# I2C_CH1.net
KiCad netlist of a schematic drawn in Altium Designer
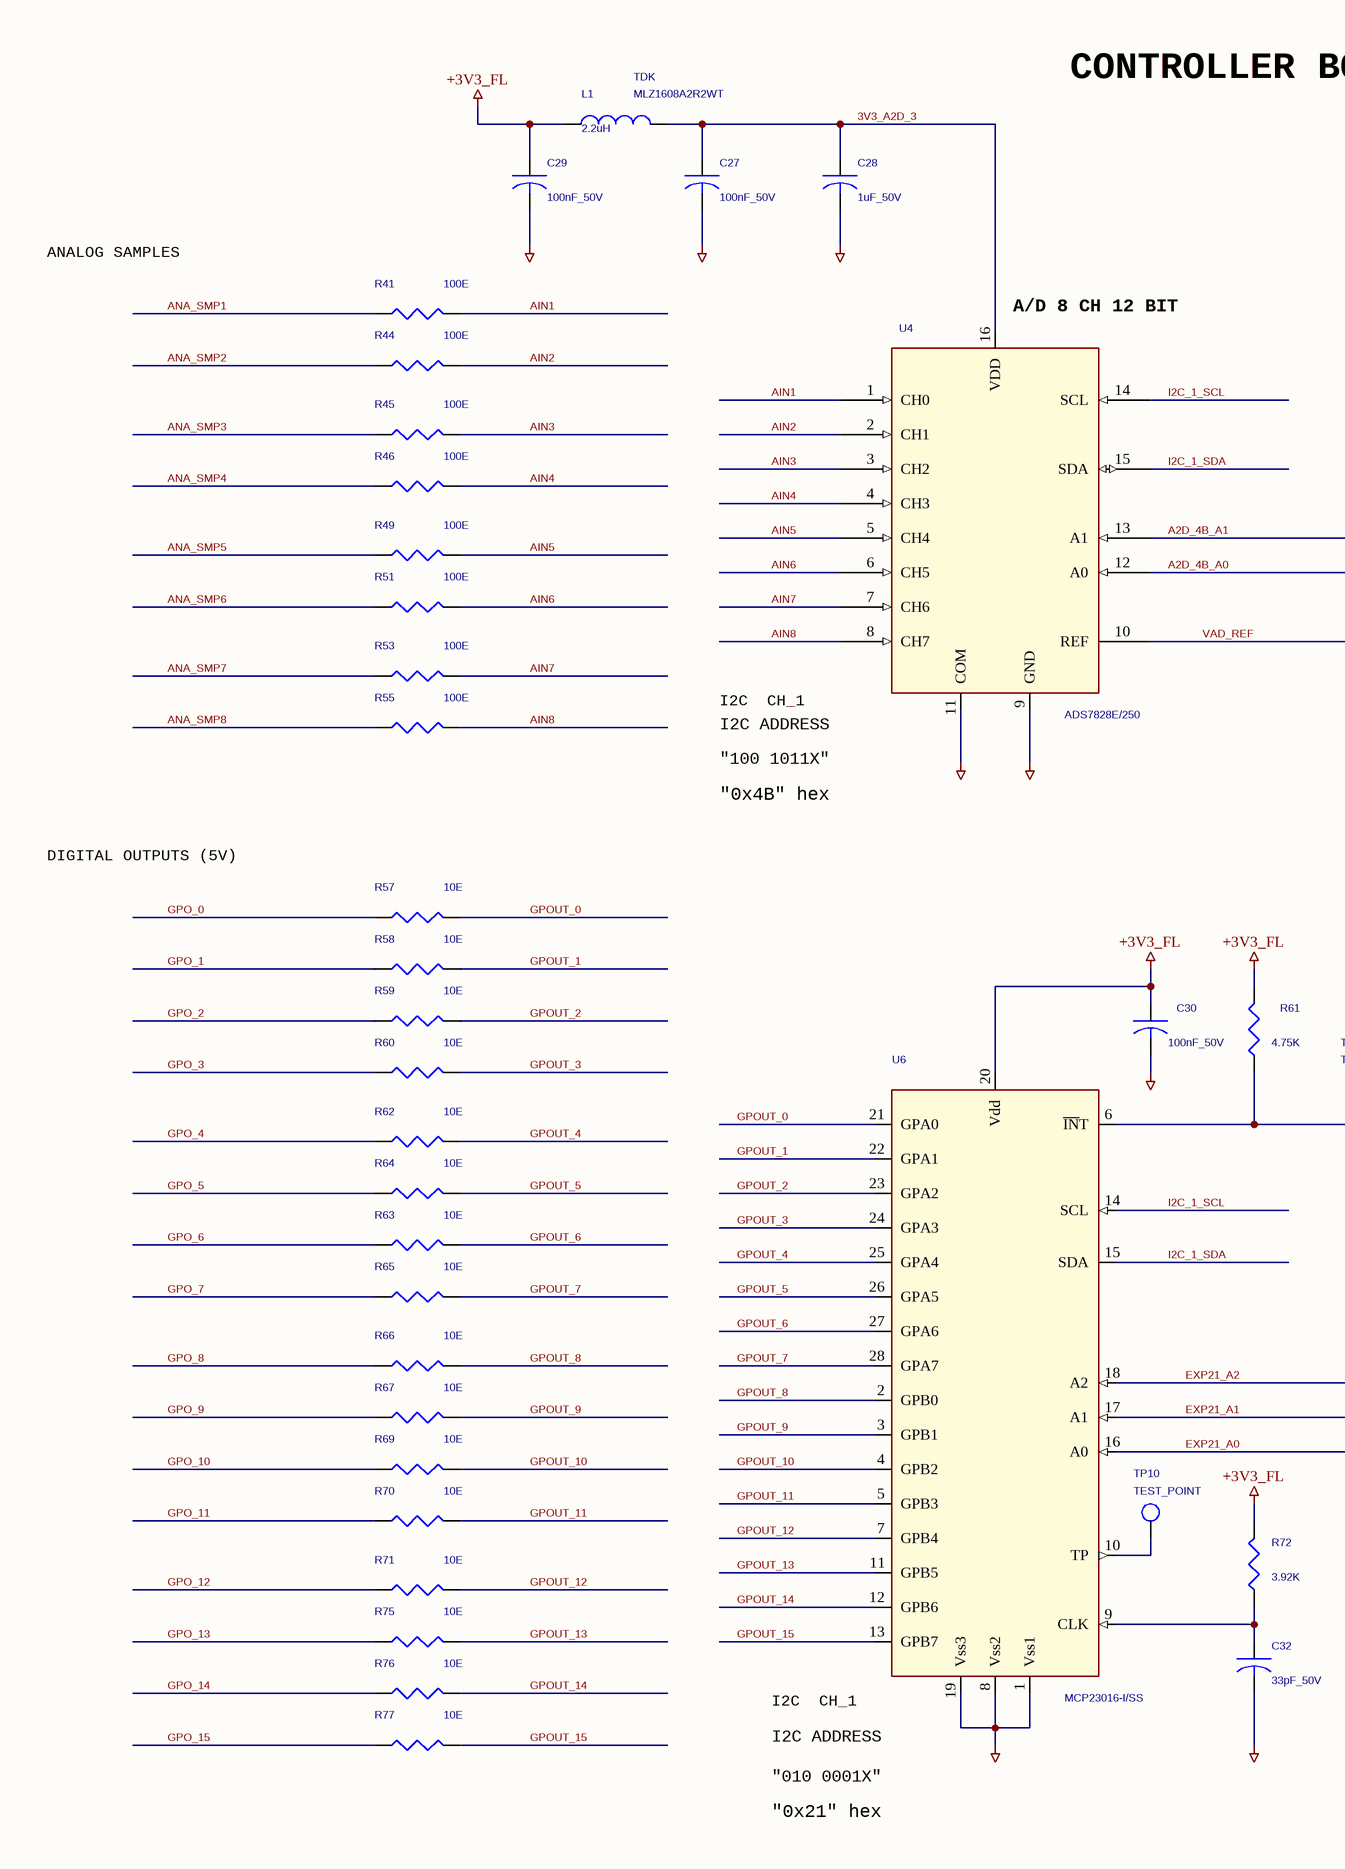
[diagram p0: I2C_CH1.SchDoc, left]
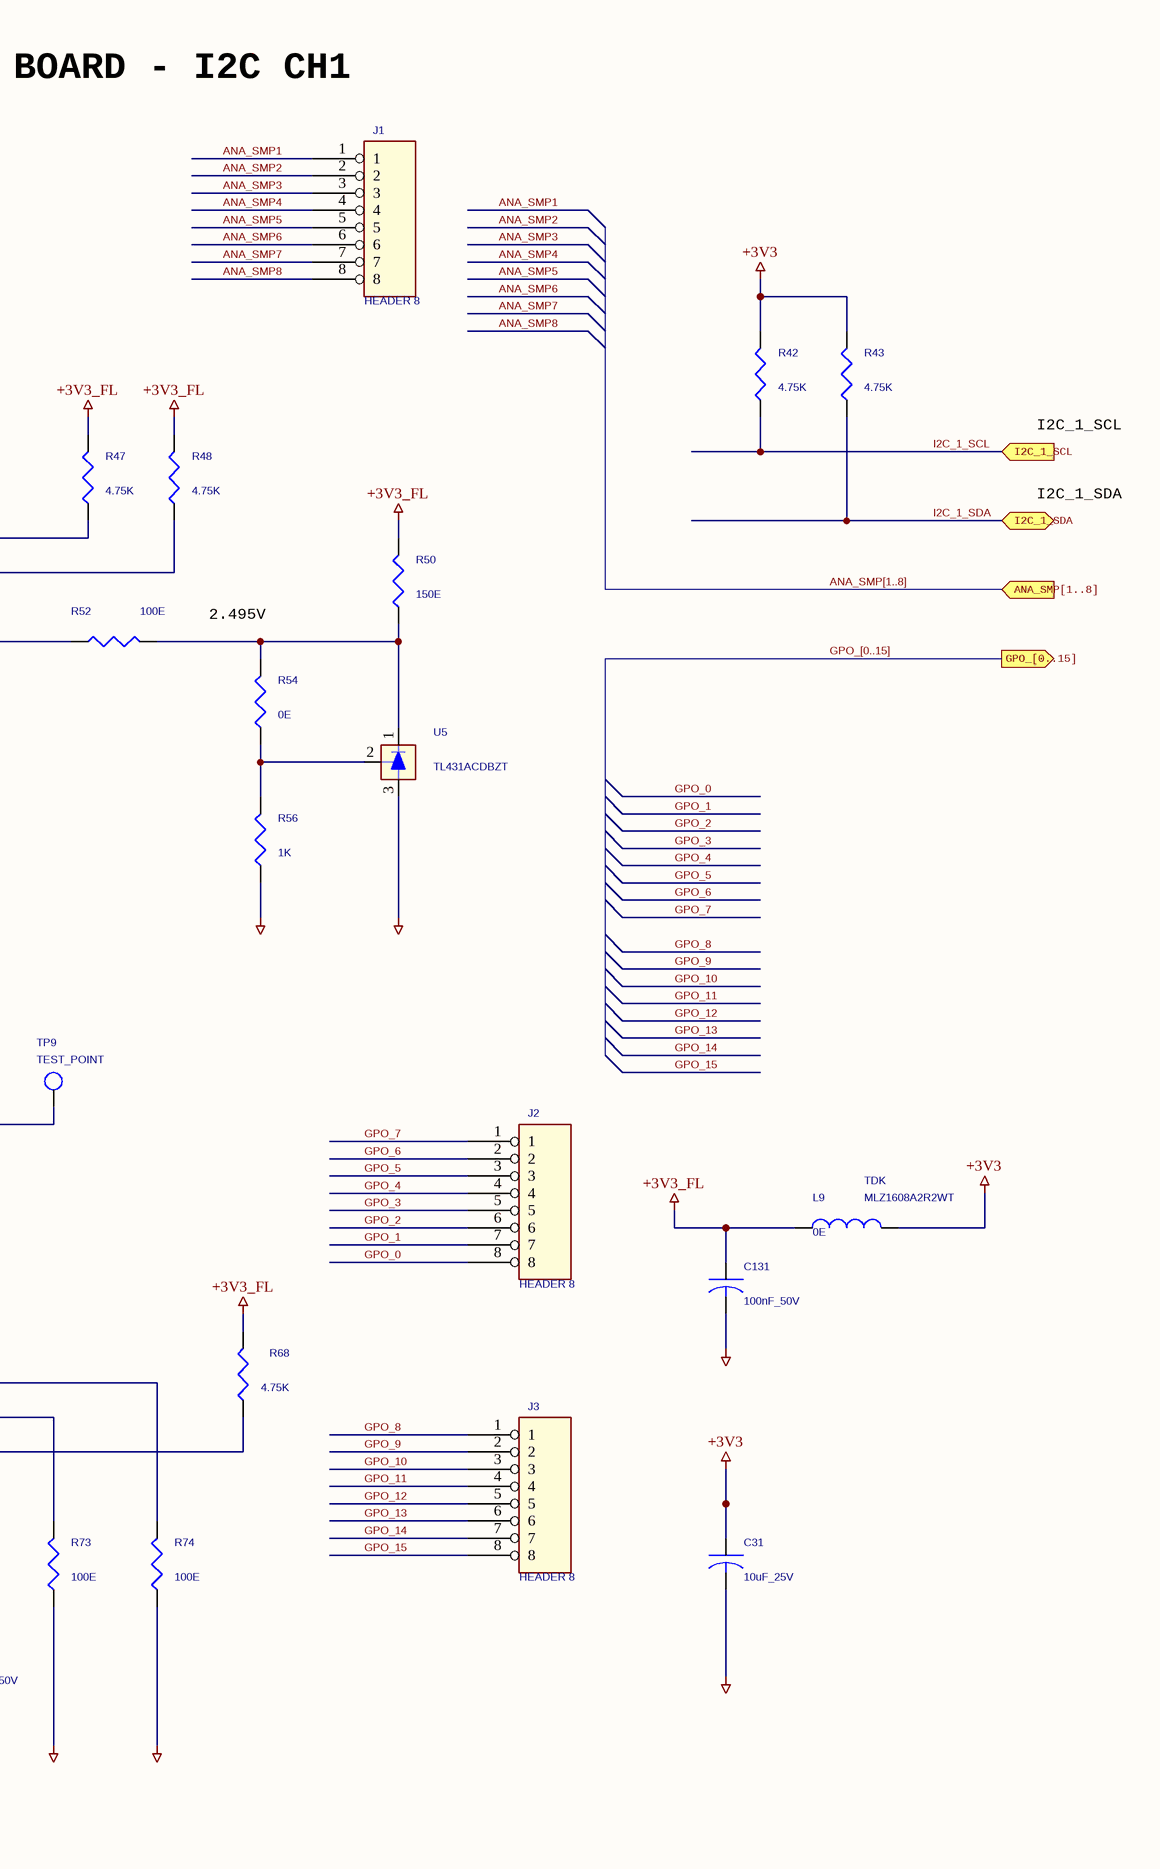
[diagram p1: I2C_CH1.SchDoc, right]

(export (version "E")
  (design (tool "Eeschema 10.0.6"))
  (components
    (comp (ref "C27")
      (value "100nF_50V")
      (footprint "0603")
      (description "CAP_SMT_0603_50V_X7R_10%")
      (fields (field (name "MFG") "KEMET"))
      (libsource (lib "*") (part "C"))
    )
    (comp (ref "C28")
      (value "1uF_50V")
      (footprint "0805")
      (description "a")
      (fields (field (name "MFG") "Murata") (field (name "MNFCTR_PART_NUMBER") "TCJT106M016R0150"))
      (libsource (lib "*") (part "CAP"))
    )
    (comp (ref "C29")
      (value "100nF_50V")
      (footprint "0603")
      (description "CAP_SMT_0603_50V_X7R_10%")
      (fields (field (name "MFG") "KEMET"))
      (libsource (lib "*") (part "C"))
    )
    (comp (ref "C30")
      (value "100nF_50V")
      (footprint "0603")
      (description "CAP_SMT_0603_50V_X7R_10%")
      (fields (field (name "MFG") "KEMET"))
      (libsource (lib "*") (part "C"))
    )
    (comp (ref "C31")
      (value "10uF_25V")
      (footprint "1206")
      (description "CAP_SMT_1206_25V_X7R_10%")
      (fields (field (name "MFG") "KEMET"))
      (libsource (lib "*") (part "C"))
    )
    (comp (ref "C32")
      (value "33pF_50V")
      (footprint "0603")
      (description "CAP_SMT_0603_50V_X7R_10%")
      (fields (field (name "MFG") "KEMET"))
      (libsource (lib "*") (part "C"))
    )
    (comp (ref "C131")
      (value "100nF_50V")
      (footprint "0603")
      (description "CAP_SMT_0603_50V_X7R_10%")
      (fields (field (name "MFG") "KEMET"))
      (libsource (lib "*") (part "C"))
    )
    (comp (ref "J1") (value "HEADER 8") (footprint "TH_8PIN_100mil") (libsource (lib "*") (part "HEADER 8")))
    (comp (ref "J2")
      (value "HEADER 8")
      (footprint "TH_8PIN_100mil")
      (libsource (lib "CONTROLLER_30") (part "HEADER 8"))
    )
    (comp (ref "J3") (value "HEADER 8") (footprint "TH_8PIN_100mil") (libsource (lib "*") (part "HEADER 8")))
    (comp (ref "L1")
      (value "2.2uH")
      (footprint "0603")
      (fields (field (name "MFG_PN") "MLZ1608A2R2WT") (field (name "MFG") "TDK"))
      (libsource (lib "*") (part "INDUCTOR"))
    )
    (comp (ref "L9")
      (value "0E")
      (footprint "0603")
      (fields (field (name "MFG") "TDK") (field (name "MFG_PN") "MLZ1608A2R2WT"))
      (libsource (lib "*") (part "INDUCTOR"))
    )
    (comp (ref "R41")
      (value "100E")
      (footprint "0603")
      (fields (field (name "MFG") "YAGEO"))
      (libsource (lib "*") (part "R_Dup1"))
    )
    (comp (ref "R42")
      (value "4.75K")
      (footprint "0603")
      (fields (field (name "MFG") "YAGEO"))
      (libsource (lib "*") (part "R_Dup1"))
    )
    (comp (ref "R43")
      (value "4.75K")
      (footprint "0603")
      (fields (field (name "MFG") "YAGEO"))
      (libsource (lib "*") (part "R_Dup1"))
    )
    (comp (ref "R44")
      (value "100E")
      (footprint "0603")
      (fields (field (name "MFG") "YAGEO"))
      (libsource (lib "*") (part "R_Dup1"))
    )
    (comp (ref "R45")
      (value "100E")
      (footprint "0603")
      (fields (field (name "MFG") "YAGEO"))
      (libsource (lib "*") (part "R_Dup1"))
    )
    (comp (ref "R46")
      (value "100E")
      (footprint "0603")
      (fields (field (name "MFG") "YAGEO"))
      (libsource (lib "*") (part "R_Dup1"))
    )
    (comp (ref "R47")
      (value "4.75K")
      (footprint "0603")
      (fields (field (name "MFG") "YAGEO"))
      (libsource (lib "*") (part "R_Dup1"))
    )
    (comp (ref "R48")
      (value "4.75K")
      (footprint "0603")
      (fields (field (name "MFG") "YAGEO"))
      (libsource (lib "*") (part "R_Dup1"))
    )
    (comp (ref "R49")
      (value "100E")
      (footprint "0603")
      (fields (field (name "MFG") "YAGEO"))
      (libsource (lib "*") (part "R_Dup1"))
    )
    (comp (ref "R50")
      (value "150E")
      (footprint "0603")
      (fields (field (name "MFG") "YAGEO"))
      (libsource (lib "*") (part "R_Dup1"))
    )
    (comp (ref "R51")
      (value "100E")
      (footprint "0603")
      (fields (field (name "MFG") "YAGEO"))
      (libsource (lib "*") (part "R_Dup1"))
    )
    (comp (ref "R52")
      (value "100E")
      (footprint "0603")
      (fields (field (name "MFG") "YAGEO"))
      (libsource (lib "*") (part "R_Dup1"))
    )
    (comp (ref "R53")
      (value "100E")
      (footprint "0603")
      (fields (field (name "MFG") "YAGEO"))
      (libsource (lib "*") (part "R_Dup1"))
    )
    (comp (ref "R54")
      (value "0E")
      (footprint "0603")
      (fields (field (name "MFG") "YAGEO"))
      (libsource (lib "*") (part "R_Dup1"))
    )
    (comp (ref "R55")
      (value "100E")
      (footprint "0603")
      (fields (field (name "MFG") "YAGEO"))
      (libsource (lib "*") (part "R_Dup1"))
    )
    (comp (ref "R56")
      (value "1K")
      (footprint "0603")
      (fields (field (name "MFG") "YAGEO"))
      (libsource (lib "*") (part "R_Dup1"))
    )
    (comp (ref "R57")
      (value "10E")
      (footprint "0603")
      (fields (field (name "MFG") "YAGEO"))
      (libsource (lib "*") (part "R_Dup1"))
    )
    (comp (ref "R58")
      (value "10E")
      (footprint "0603")
      (fields (field (name "MFG") "YAGEO"))
      (libsource (lib "*") (part "R_Dup1"))
    )
    (comp (ref "R59")
      (value "10E")
      (footprint "0603")
      (fields (field (name "MFG") "YAGEO"))
      (libsource (lib "*") (part "R_Dup1"))
    )
    (comp (ref "R60")
      (value "10E")
      (footprint "0603")
      (fields (field (name "MFG") "YAGEO"))
      (libsource (lib "*") (part "R_Dup1"))
    )
    (comp (ref "R61")
      (value "4.75K")
      (footprint "0603")
      (fields (field (name "MFG") "YAGEO"))
      (libsource (lib "*") (part "R_Dup1"))
    )
    (comp (ref "R62")
      (value "10E")
      (footprint "0603")
      (fields (field (name "MFG") "YAGEO"))
      (libsource (lib "*") (part "R_Dup1"))
    )
    (comp (ref "R63")
      (value "10E")
      (footprint "0603")
      (fields (field (name "MFG") "YAGEO"))
      (libsource (lib "*") (part "R_Dup1"))
    )
    (comp (ref "R64")
      (value "10E")
      (footprint "0603")
      (fields (field (name "MFG") "YAGEO"))
      (libsource (lib "*") (part "R_Dup1"))
    )
    (comp (ref "R65")
      (value "10E")
      (footprint "0603")
      (fields (field (name "MFG") "YAGEO"))
      (libsource (lib "*") (part "R_Dup1"))
    )
    (comp (ref "R66")
      (value "10E")
      (footprint "0603")
      (fields (field (name "MFG") "YAGEO"))
      (libsource (lib "*") (part "R_Dup1"))
    )
    (comp (ref "R67")
      (value "10E")
      (footprint "0603")
      (fields (field (name "MFG") "YAGEO"))
      (libsource (lib "*") (part "R_Dup1"))
    )
    (comp (ref "R68")
      (value "4.75K")
      (footprint "0603")
      (fields (field (name "MFG") "YAGEO"))
      (libsource (lib "*") (part "R_Dup1"))
    )
    (comp (ref "R69")
      (value "10E")
      (footprint "0603")
      (fields (field (name "MFG") "YAGEO"))
      (libsource (lib "*") (part "R_Dup1"))
    )
    (comp (ref "R70")
      (value "10E")
      (footprint "0603")
      (fields (field (name "MFG") "YAGEO"))
      (libsource (lib "*") (part "R_Dup1"))
    )
    (comp (ref "R71")
      (value "10E")
      (footprint "0603")
      (fields (field (name "MFG") "YAGEO"))
      (libsource (lib "*") (part "R_Dup1"))
    )
    (comp (ref "R72")
      (value "3.92K")
      (footprint "0603")
      (fields (field (name "MFG") "YAGEO"))
      (libsource (lib "*") (part "R_Dup1"))
    )
    (comp (ref "R73")
      (value "100E")
      (footprint "0603")
      (fields (field (name "MFG") "YAGEO"))
      (libsource (lib "*") (part "R_Dup1"))
    )
    (comp (ref "R74")
      (value "100E")
      (footprint "0603")
      (fields (field (name "MFG") "YAGEO"))
      (libsource (lib "*") (part "R_Dup1"))
    )
    (comp (ref "R75")
      (value "10E")
      (footprint "0603")
      (fields (field (name "MFG") "YAGEO"))
      (libsource (lib "*") (part "R_Dup1"))
    )
    (comp (ref "R76")
      (value "10E")
      (footprint "0603")
      (fields (field (name "MFG") "YAGEO"))
      (libsource (lib "*") (part "R_Dup1"))
    )
    (comp (ref "R77")
      (value "10E")
      (footprint "0603")
      (fields (field (name "MFG") "YAGEO"))
      (libsource (lib "*") (part "R_Dup1"))
    )
    (comp (ref "TP9") (value "TEST_POINT") (footprint "TH_1mm") (libsource (lib "*") (part "T POINT R_Dup1")))
    (comp (ref "TP10")
      (value "TEST_POINT")
      (footprint "TH_1mm")
      (libsource (lib "*") (part "T POINT R_Dup1"))
    )
    (comp (ref "U4")
      (value "ADS7828E/250")
      (footprint "TSSOP_16")
      (fields (field (name "MFG") "TI"))
      (libsource (lib "*") (part "ADS7828E"))
    )
    (comp (ref "U5")
      (value "TL431ACDBZT")
      (footprint "SOT_23")
      (fields (field (name "PART_NUMBER") "<Part_Number>") (field (name "MFG") "TI"))
      (libsource (lib "*") (part "TL431ACDBZT"))
    )
    (comp (ref "U6")
      (value "MCP23016-I/SS")
      (footprint "SSOP_28")
      (fields (field (name "MFG") "MICROCHIP"))
      (libsource (lib "*") (part "MCP23016-I/SS"))
    )
  )
  (nets
    (net (code "1") (name "+3V3") (class "Default")
      (node (ref "C31") (pin "1") (pinfunction "1_1") (pintype "passive"))
      (node (ref "L9") (pin "2") (pinfunction "2_2") (pintype "passive"))
      (node (ref "R42") (pin "2") (pinfunction "2_2") (pintype "passive"))
      (node (ref "R43") (pin "2") (pinfunction "2_2") (pintype "passive"))
    )
    (net (code "2") (name "+3V3_FL") (class "Default")
      (node (ref "C131") (pin "1") (pinfunction "1_1") (pintype "passive"))
      (node (ref "C29") (pin "1") (pinfunction "1_1") (pintype "passive"))
      (node (ref "C30") (pin "1") (pinfunction "1_1") (pintype "passive"))
      (node (ref "L1") (pin "1") (pinfunction "1_1") (pintype "passive"))
      (node (ref "L9") (pin "1") (pinfunction "1_1") (pintype "passive"))
      (node (ref "R47") (pin "2") (pinfunction "2_2") (pintype "passive"))
      (node (ref "R48") (pin "2") (pinfunction "2_2") (pintype "passive"))
      (node (ref "R50") (pin "2") (pinfunction "2_2") (pintype "passive"))
      (node (ref "R61") (pin "2") (pinfunction "2_2") (pintype "passive"))
      (node (ref "R68") (pin "2") (pinfunction "2_2") (pintype "passive"))
      (node (ref "R72") (pin "2") (pinfunction "2_2") (pintype "passive"))
      (node (ref "U6") (pin "20") (pinfunction "Vdd_20") (pintype "passive"))
    )
    (net (code "3") (name "/3V3_A2D_3") (class "Default")
      (node (ref "C27") (pin "1") (pinfunction "1_1") (pintype "passive"))
      (node (ref "C28") (pin "1") (pinfunction "1_1") (pintype "passive"))
      (node (ref "L1") (pin "2") (pinfunction "2_2") (pintype "passive"))
      (node (ref "U4") (pin "16") (pinfunction "VDD_16") (pintype "passive"))
    )
    (net (code "4") (name "/A2D_4B_A0") (class "Default")
      (node (ref "R48") (pin "1") (pinfunction "1_1") (pintype "passive"))
      (node (ref "U4") (pin "12") (pinfunction "A0_12") (pintype "input"))
    )
    (net (code "5") (name "/A2D_4B_A1") (class "Default")
      (node (ref "R47") (pin "1") (pinfunction "1_1") (pintype "passive"))
      (node (ref "U4") (pin "13") (pinfunction "A1_13") (pintype "input"))
    )
    (net (code "6") (name "/AIN1") (class "Default")
      (node (ref "R41") (pin "1") (pinfunction "1_1") (pintype "passive"))
      (node (ref "U4") (pin "1") (pinfunction "CH0_1") (pintype "input"))
    )
    (net (code "7") (name "/AIN2") (class "Default")
      (node (ref "R44") (pin "1") (pinfunction "1_1") (pintype "passive"))
      (node (ref "U4") (pin "2") (pinfunction "CH1_2") (pintype "input"))
    )
    (net (code "8") (name "/AIN3") (class "Default")
      (node (ref "R45") (pin "1") (pinfunction "1_1") (pintype "passive"))
      (node (ref "U4") (pin "3") (pinfunction "CH2_3") (pintype "input"))
    )
    (net (code "9") (name "/AIN4") (class "Default")
      (node (ref "R46") (pin "1") (pinfunction "1_1") (pintype "passive"))
      (node (ref "U4") (pin "4") (pinfunction "CH3_4") (pintype "input"))
    )
    (net (code "10") (name "/AIN5") (class "Default")
      (node (ref "R49") (pin "1") (pinfunction "1_1") (pintype "passive"))
      (node (ref "U4") (pin "5") (pinfunction "CH4_5") (pintype "input"))
    )
    (net (code "11") (name "/AIN6") (class "Default")
      (node (ref "R51") (pin "1") (pinfunction "1_1") (pintype "passive"))
      (node (ref "U4") (pin "6") (pinfunction "CH5_6") (pintype "input"))
    )
    (net (code "12") (name "/AIN7") (class "Default")
      (node (ref "R53") (pin "1") (pinfunction "1_1") (pintype "passive"))
      (node (ref "U4") (pin "7") (pinfunction "CH6_7") (pintype "input"))
    )
    (net (code "13") (name "/AIN8") (class "Default")
      (node (ref "R55") (pin "1") (pinfunction "1_1") (pintype "passive"))
      (node (ref "U4") (pin "8") (pinfunction "CH7_8") (pintype "input"))
    )
    (net (code "14") (name "/ANA_SMP1") (class "Default")
      (node (ref "J1") (pin "1") (pinfunction "1_1") (pintype "passive"))
      (node (ref "R41") (pin "2") (pinfunction "2_2") (pintype "passive"))
    )
    (net (code "15") (name "/ANA_SMP2") (class "Default")
      (node (ref "J1") (pin "2") (pinfunction "2_2") (pintype "passive"))
      (node (ref "R44") (pin "2") (pinfunction "2_2") (pintype "passive"))
    )
    (net (code "16") (name "/ANA_SMP3") (class "Default")
      (node (ref "J1") (pin "3") (pinfunction "3_3") (pintype "passive"))
      (node (ref "R45") (pin "2") (pinfunction "2_2") (pintype "passive"))
    )
    (net (code "17") (name "/ANA_SMP4") (class "Default")
      (node (ref "J1") (pin "4") (pinfunction "4_4") (pintype "passive"))
      (node (ref "R46") (pin "2") (pinfunction "2_2") (pintype "passive"))
    )
    (net (code "18") (name "/ANA_SMP5") (class "Default")
      (node (ref "J1") (pin "5") (pinfunction "5_5") (pintype "passive"))
      (node (ref "R49") (pin "2") (pinfunction "2_2") (pintype "passive"))
    )
    (net (code "19") (name "/ANA_SMP6") (class "Default")
      (node (ref "J1") (pin "6") (pinfunction "6_6") (pintype "passive"))
      (node (ref "R51") (pin "2") (pinfunction "2_2") (pintype "passive"))
    )
    (net (code "20") (name "/ANA_SMP7") (class "Default")
      (node (ref "J1") (pin "7") (pinfunction "7_7") (pintype "passive"))
      (node (ref "R53") (pin "2") (pinfunction "2_2") (pintype "passive"))
    )
    (net (code "21") (name "/ANA_SMP8") (class "Default")
      (node (ref "J1") (pin "8") (pinfunction "8_8") (pintype "passive"))
      (node (ref "R55") (pin "2") (pinfunction "2_2") (pintype "passive"))
    )
    (net (code "23") (name "/EXP21_A0") (class "Default")
      (node (ref "R68") (pin "1") (pinfunction "1_1") (pintype "passive"))
      (node (ref "U6") (pin "16") (pinfunction "A0_16") (pintype "input"))
    )
    (net (code "24") (name "/EXP21_A1") (class "Default")
      (node (ref "R73") (pin "2") (pinfunction "2_2") (pintype "passive"))
      (node (ref "U6") (pin "17") (pinfunction "A1_17") (pintype "input"))
    )
    (net (code "25") (name "/EXP21_A2") (class "Default")
      (node (ref "R74") (pin "2") (pinfunction "2_2") (pintype "passive"))
      (node (ref "U6") (pin "18") (pinfunction "A2_18") (pintype "input"))
    )
    (net (code "26") (name "/GPOUT_0") (class "Default")
      (node (ref "R57") (pin "1") (pinfunction "1_1") (pintype "passive"))
      (node (ref "U6") (pin "21") (pinfunction "GPA0_21") (pintype "bidirectional"))
    )
    (net (code "27") (name "/GPOUT_1") (class "Default")
      (node (ref "R58") (pin "1") (pinfunction "1_1") (pintype "passive"))
      (node (ref "U6") (pin "22") (pinfunction "GPA1_22") (pintype "bidirectional"))
    )
    (net (code "28") (name "/GPOUT_2") (class "Default")
      (node (ref "R59") (pin "1") (pinfunction "1_1") (pintype "passive"))
      (node (ref "U6") (pin "23") (pinfunction "GPA2_23") (pintype "bidirectional"))
    )
    (net (code "29") (name "/GPOUT_3") (class "Default")
      (node (ref "R60") (pin "1") (pinfunction "1_1") (pintype "passive"))
      (node (ref "U6") (pin "24") (pinfunction "GPA3_24") (pintype "bidirectional"))
    )
    (net (code "30") (name "/GPOUT_4") (class "Default")
      (node (ref "R62") (pin "1") (pinfunction "1_1") (pintype "passive"))
      (node (ref "U6") (pin "25") (pinfunction "GPA4_25") (pintype "bidirectional"))
    )
    (net (code "31") (name "/GPOUT_5") (class "Default")
      (node (ref "R64") (pin "1") (pinfunction "1_1") (pintype "passive"))
      (node (ref "U6") (pin "26") (pinfunction "GPA5_26") (pintype "bidirectional"))
    )
    (net (code "32") (name "/GPOUT_6") (class "Default")
      (node (ref "R63") (pin "1") (pinfunction "1_1") (pintype "passive"))
      (node (ref "U6") (pin "27") (pinfunction "GPA6_27") (pintype "bidirectional"))
    )
    (net (code "33") (name "/GPOUT_7") (class "Default")
      (node (ref "R65") (pin "1") (pinfunction "1_1") (pintype "passive"))
      (node (ref "U6") (pin "28") (pinfunction "GPA7_28") (pintype "bidirectional"))
    )
    (net (code "34") (name "/GPOUT_8") (class "Default")
      (node (ref "R66") (pin "1") (pinfunction "1_1") (pintype "passive"))
      (node (ref "U6") (pin "2") (pinfunction "GPB0_2") (pintype "bidirectional"))
    )
    (net (code "35") (name "/GPOUT_9") (class "Default")
      (node (ref "R67") (pin "1") (pinfunction "1_1") (pintype "passive"))
      (node (ref "U6") (pin "3") (pinfunction "GPB1_3") (pintype "bidirectional"))
    )
    (net (code "36") (name "/GPOUT_10") (class "Default")
      (node (ref "R69") (pin "1") (pinfunction "1_1") (pintype "passive"))
      (node (ref "U6") (pin "4") (pinfunction "GPB2_4") (pintype "bidirectional"))
    )
    (net (code "37") (name "/GPOUT_11") (class "Default")
      (node (ref "R70") (pin "1") (pinfunction "1_1") (pintype "passive"))
      (node (ref "U6") (pin "5") (pinfunction "GPB3_5") (pintype "bidirectional"))
    )
    (net (code "38") (name "/GPOUT_12") (class "Default")
      (node (ref "R71") (pin "1") (pinfunction "1_1") (pintype "passive"))
      (node (ref "U6") (pin "7") (pinfunction "GPB4_7") (pintype "bidirectional"))
    )
    (net (code "39") (name "/GPOUT_13") (class "Default")
      (node (ref "R75") (pin "1") (pinfunction "1_1") (pintype "passive"))
      (node (ref "U6") (pin "11") (pinfunction "GPB5_11") (pintype "bidirectional"))
    )
    (net (code "40") (name "/GPOUT_14") (class "Default")
      (node (ref "R76") (pin "1") (pinfunction "1_1") (pintype "passive"))
      (node (ref "U6") (pin "12") (pinfunction "GPB6_12") (pintype "bidirectional"))
    )
    (net (code "41") (name "/GPOUT_15") (class "Default")
      (node (ref "R77") (pin "1") (pinfunction "1_1") (pintype "passive"))
      (node (ref "U6") (pin "13") (pinfunction "GPB7_13") (pintype "bidirectional"))
    )
    (net (code "42") (name "/GPO_0") (class "Default")
      (node (ref "J2") (pin "8") (pinfunction "8_8") (pintype "passive"))
      (node (ref "R57") (pin "2") (pinfunction "2_2") (pintype "passive"))
    )
    (net (code "43") (name "/GPO_1") (class "Default")
      (node (ref "J2") (pin "7") (pinfunction "7_7") (pintype "passive"))
      (node (ref "R58") (pin "2") (pinfunction "2_2") (pintype "passive"))
    )
    (net (code "44") (name "/GPO_2") (class "Default")
      (node (ref "J2") (pin "6") (pinfunction "6_6") (pintype "passive"))
      (node (ref "R59") (pin "2") (pinfunction "2_2") (pintype "passive"))
    )
    (net (code "45") (name "/GPO_3") (class "Default")
      (node (ref "J2") (pin "5") (pinfunction "5_5") (pintype "passive"))
      (node (ref "R60") (pin "2") (pinfunction "2_2") (pintype "passive"))
    )
    (net (code "46") (name "/GPO_4") (class "Default")
      (node (ref "J2") (pin "4") (pinfunction "4_4") (pintype "passive"))
      (node (ref "R62") (pin "2") (pinfunction "2_2") (pintype "passive"))
    )
    (net (code "47") (name "/GPO_5") (class "Default")
      (node (ref "J2") (pin "3") (pinfunction "3_3") (pintype "passive"))
      (node (ref "R64") (pin "2") (pinfunction "2_2") (pintype "passive"))
    )
    (net (code "48") (name "/GPO_6") (class "Default")
      (node (ref "J2") (pin "2") (pinfunction "2_2") (pintype "passive"))
      (node (ref "R63") (pin "2") (pinfunction "2_2") (pintype "passive"))
    )
    (net (code "49") (name "/GPO_7") (class "Default")
      (node (ref "J2") (pin "1") (pinfunction "1_1") (pintype "passive"))
      (node (ref "R65") (pin "2") (pinfunction "2_2") (pintype "passive"))
    )
    (net (code "50") (name "/GPO_8") (class "Default")
      (node (ref "J3") (pin "1") (pinfunction "1_1") (pintype "passive"))
      (node (ref "R66") (pin "2") (pinfunction "2_2") (pintype "passive"))
    )
    (net (code "51") (name "/GPO_9") (class "Default")
      (node (ref "J3") (pin "2") (pinfunction "2_2") (pintype "passive"))
      (node (ref "R67") (pin "2") (pinfunction "2_2") (pintype "passive"))
    )
    (net (code "52") (name "/GPO_10") (class "Default")
      (node (ref "J3") (pin "3") (pinfunction "3_3") (pintype "passive"))
      (node (ref "R69") (pin "2") (pinfunction "2_2") (pintype "passive"))
    )
    (net (code "53") (name "/GPO_11") (class "Default")
      (node (ref "J3") (pin "4") (pinfunction "4_4") (pintype "passive"))
      (node (ref "R70") (pin "2") (pinfunction "2_2") (pintype "passive"))
    )
    (net (code "54") (name "/GPO_12") (class "Default")
      (node (ref "J3") (pin "5") (pinfunction "5_5") (pintype "passive"))
      (node (ref "R71") (pin "2") (pinfunction "2_2") (pintype "passive"))
    )
    (net (code "55") (name "/GPO_13") (class "Default")
      (node (ref "J3") (pin "6") (pinfunction "6_6") (pintype "passive"))
      (node (ref "R75") (pin "2") (pinfunction "2_2") (pintype "passive"))
    )
    (net (code "56") (name "/GPO_14") (class "Default")
      (node (ref "J3") (pin "7") (pinfunction "7_7") (pintype "passive"))
      (node (ref "R76") (pin "2") (pinfunction "2_2") (pintype "passive"))
    )
    (net (code "57") (name "/GPO_15") (class "Default")
      (node (ref "J3") (pin "8") (pinfunction "8_8") (pintype "passive"))
      (node (ref "R77") (pin "2") (pinfunction "2_2") (pintype "passive"))
    )
    (net (code "59") (name "/I2C_1_SCL") (class "Default")
      (node (ref "R42") (pin "1") (pinfunction "1_1") (pintype "passive"))
      (node (ref "U4") (pin "14") (pinfunction "SCL_14") (pintype "input"))
      (node (ref "U6") (pin "14") (pinfunction "SCL_14") (pintype "input"))
    )
    (net (code "60") (name "/I2C_1_SDA") (class "Default")
      (node (ref "R43") (pin "1") (pinfunction "1_1") (pintype "passive"))
      (node (ref "U4") (pin "15") (pinfunction "SDA_15") (pintype "bidirectional"))
      (node (ref "U6") (pin "15") (pinfunction "SDA_15") (pintype "bidirectional"))
    )
    (net (code "61") (name "/VAD_REF") (class "Default")
      (node (ref "R52") (pin "2") (pinfunction "2_2") (pintype "passive"))
      (node (ref "U4") (pin "10") (pinfunction "REF_10") (pintype "passive"))
    )
    (net (code "62") (name "GND_CPU") (class "Default")
      (node (ref "C131") (pin "2") (pinfunction "2_2") (pintype "passive"))
      (node (ref "C27") (pin "2") (pinfunction "2_2") (pintype "passive"))
      (node (ref "C28") (pin "2") (pinfunction "2_2") (pintype "passive"))
      (node (ref "C29") (pin "2") (pinfunction "2_2") (pintype "passive"))
      (node (ref "C30") (pin "2") (pinfunction "2_2") (pintype "passive"))
      (node (ref "C31") (pin "2") (pinfunction "2_2") (pintype "passive"))
      (node (ref "C32") (pin "2") (pinfunction "2_2") (pintype "passive"))
      (node (ref "R56") (pin "1") (pinfunction "1_1") (pintype "passive"))
      (node (ref "R73") (pin "1") (pinfunction "1_1") (pintype "passive"))
      (node (ref "R74") (pin "1") (pinfunction "1_1") (pintype "passive"))
      (node (ref "U4") (pin "11") (pinfunction "COM_11") (pintype "passive"))
      (node (ref "U4") (pin "9") (pinfunction "GND_9") (pintype "passive"))
      (node (ref "U5") (pin "3") (pinfunction "ANODA_3") (pintype "passive"))
      (node (ref "U6") (pin "1") (pinfunction "Vss1_1") (pintype "passive"))
      (node (ref "U6") (pin "19") (pinfunction "Vss3_19") (pintype "passive"))
      (node (ref "U6") (pin "8") (pinfunction "Vss2_8") (pintype "passive"))
    )
    (net (code "63") (name "Net-(TP9-TP)") (class "Default")
      (node (ref "R61") (pin "1") (pinfunction "1_1") (pintype "passive"))
      (node (ref "TP9") (pin "1") (pinfunction "TP_1") (pintype "passive"))
      (node (ref "U6") (pin "6") (pinfunction "~{IN}T_6") (pintype "open_collector"))
    )
    (net (code "64") (name "Net-(TP10-TP)") (class "Default")
      (node (ref "TP10") (pin "1") (pinfunction "TP_1") (pintype "passive"))
      (node (ref "U6") (pin "10") (pinfunction "TP_10") (pintype "output"))
    )
    (net (code "65") (name "Net-(U5-CAT)") (class "Default")
      (node (ref "R50") (pin "1") (pinfunction "1_1") (pintype "passive"))
      (node (ref "R52") (pin "1") (pinfunction "1_1") (pintype "passive"))
      (node (ref "R54") (pin "2") (pinfunction "2_2") (pintype "passive"))
      (node (ref "U5") (pin "1") (pinfunction "CAT_1") (pintype "passive"))
    )
    (net (code "66") (name "Net-(U5-Vref)") (class "Default")
      (node (ref "R54") (pin "1") (pinfunction "1_1") (pintype "passive"))
      (node (ref "R56") (pin "2") (pinfunction "2_2") (pintype "passive"))
      (node (ref "U5") (pin "2") (pinfunction "Vref_2") (pintype "passive"))
    )
    (net (code "67") (name "Net-(U6-CLK)") (class "Default")
      (node (ref "C32") (pin "1") (pinfunction "1_1") (pintype "passive"))
      (node (ref "R72") (pin "1") (pinfunction "1_1") (pintype "passive"))
      (node (ref "U6") (pin "9") (pinfunction "CLK_9") (pintype "input"))
    )
  )
)
